# 0-Hierarchy.net
KiCad netlist of a schematic drawn in Altium Designer
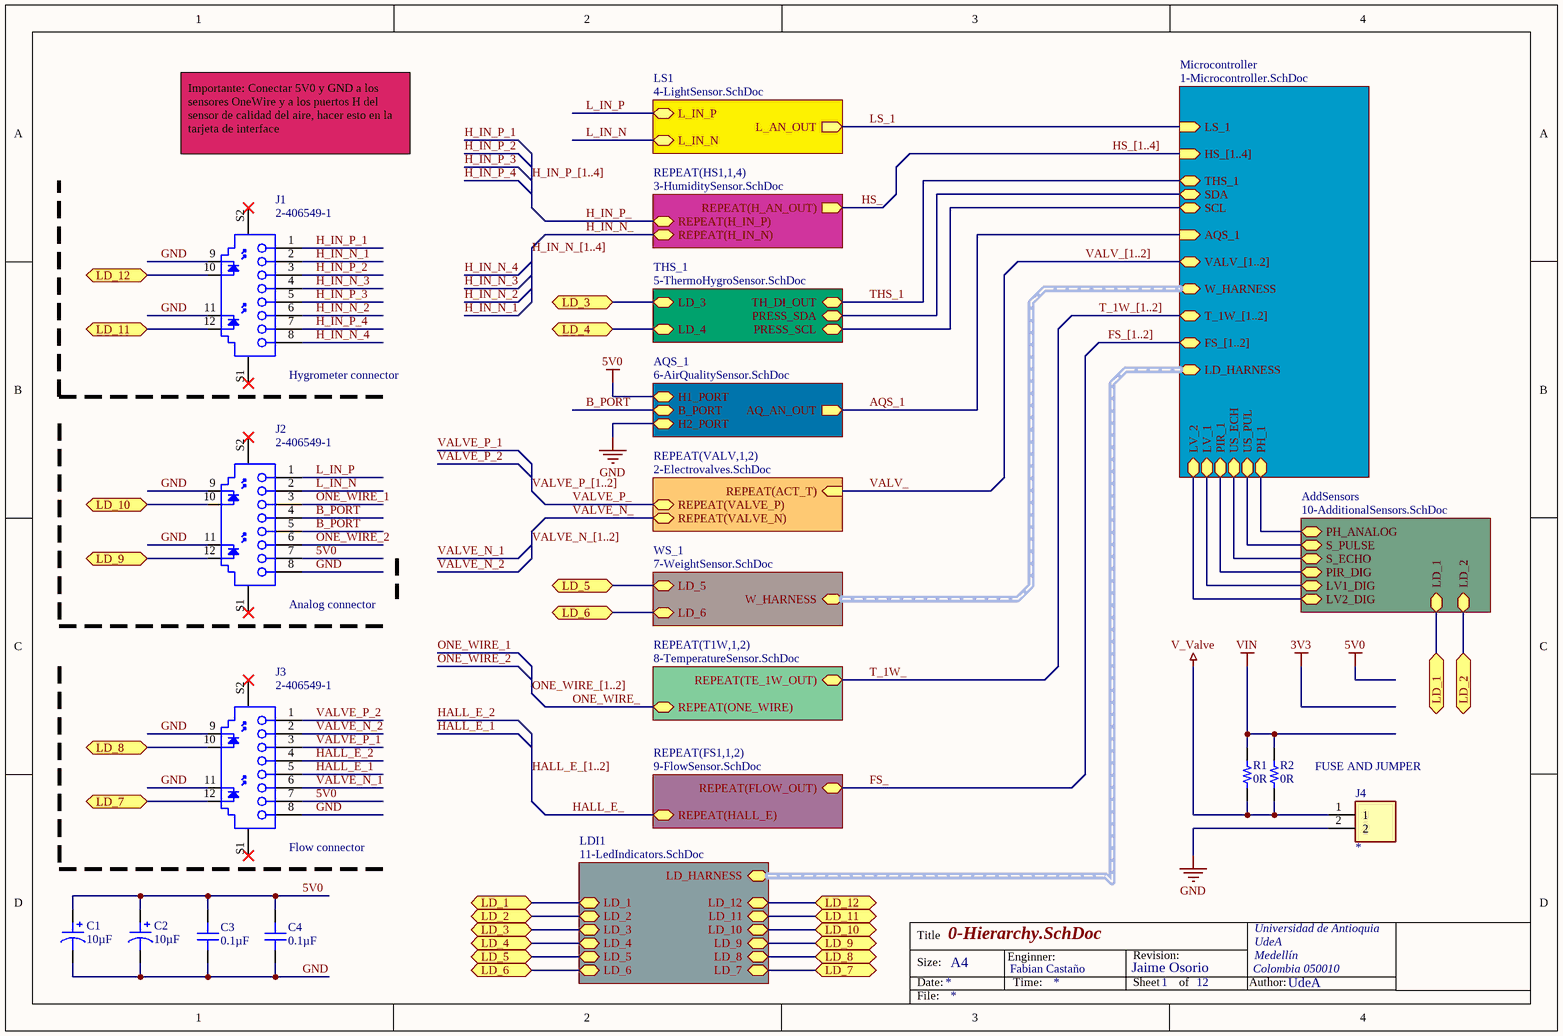
[diagram p0: 0-Hierarchy.SchDoc]

(export (version "E")
  (design (tool "Eeschema 10.0.6"))
  (components
    (comp (ref "C1")
      (value "10µF")
      (footprint "CAP POL 1206_3216")
      (description "CAP TANT POLY 10UF 25V 1206")
      (fields (field (name "PART NUMBER") "TCNK106M025R0350") (field (name "MANUFACTURER") "AVX Corporation"))
      (libsource (lib "Celestial Altium Library - altium_library") (part "Polarised Capacitor"))
    )
    (comp (ref "C2")
      (value "10µF")
      (footprint "CAP POL 1206_3216")
      (description "CAP TANT POLY 10UF 25V 1206")
      (fields (field (name "PART NUMBER") "TCNK106M025R0350") (field (name "MANUFACTURER") "AVX Corporation"))
      (libsource (lib "Celestial Altium Library - altium_library") (part "Polarised Capacitor"))
    )
    (comp (ref "C3")
      (value "0.1µF")
      (footprint "CAP 0805_2012")
      (description "CAP CER 0.1UF 50V X7R 0805")
      (fields (field (name "PART NUMBER") "C0805C104M5RACAUTO") (field (name "MANUFACTURER") "KEMET"))
      (libsource (lib "Celestial Altium Library - altium_library") (part "Capacitor"))
    )
    (comp (ref "C4")
      (value "0.1µF")
      (footprint "CAP 0805_2012")
      (description "CAP CER 0.1UF 50V X7R 0805")
      (fields (field (name "PART NUMBER") "C0805C104M5RACAUTO") (field (name "MANUFACTURER") "KEMET"))
      (libsource (lib "Celestial Altium Library - altium_library") (part "Capacitor"))
    )
    (comp (ref "J1")
      (value "2-406549-1")
      (footprint "TECO-2-406549-1_V")
      (description "RJ45 Connector, Pitch 1.016 mm, 8 Position, Height 14.22 mm, Tail Length 3.18 mm, RoHS, Tray")
      (fields (field (name "MANUFACTURER") "TE Connectivity"))
      (libsource (lib "Altium Content Vault") (part "RJ45-12-2SHLD_A"))
    )
    (comp (ref "J2")
      (value "2-406549-1")
      (footprint "TECO-2-406549-1_V")
      (description "RJ45 Connector, Pitch 1.016 mm, 8 Position, Height 14.22 mm, Tail Length 3.18 mm, RoHS, Tray")
      (fields (field (name "MANUFACTURER") "TE Connectivity"))
      (libsource (lib "Altium Content Vault") (part "RJ45-12-2SHLD_A"))
    )
    (comp (ref "J3")
      (value "2-406549-1")
      (footprint "TECO-2-406549-1_V")
      (description "RJ45 Connector, Pitch 1.016 mm, 8 Position, Height 14.22 mm, Tail Length 3.18 mm, RoHS, Tray")
      (fields (field (name "MANUFACTURER") "TE Connectivity"))
      (libsource (lib "Altium Content Vault") (part "RJ45-12-2SHLD_A"))
    )
    (comp (ref "J4")
      (value "282841-2")
      (footprint "TE_282841-2")
      (description "Conn Terminal Block 2 POS 5.08mm Solder ST Thru-Hole 17.5A/Contact")
      (fields (field (name "MF") "TE Connectivity") (field (name "COMMENT_1") "*"))
      (libsource (lib "PTR500-2") (part "282841-2"))
    )
    (comp (ref "R1")
      (value "0R")
      (footprint "RES 0805_2012")
      (description "RES SMD 1.47K OHM 1% 1/8W 0805")
      (fields (field (name "PART NUMBER") "RC0805FR-071K47L") (field (name "MANUFACTURER") "Yageo"))
      (libsource (lib "Celestial Altium Library - altium_library") (part "Resistor"))
    )
    (comp (ref "R2")
      (value "0R")
      (footprint "RES 0805_2012")
      (description "RES SMD 1.47K OHM 1% 1/8W 0805")
      (fields (field (name "PART NUMBER") "RC0805FR-071K47L") (field (name "MANUFACTURER") "Yageo"))
      (libsource (lib "Celestial Altium Library - altium_library") (part "Resistor"))
    )
  )
  (nets
    (net (code "12") (name "/B_PORT") (class "Default")
      (node (ref "J2") (pin "4") (pinfunction "4_4") (pintype "passive"))
      (node (ref "J2") (pin "5") (pinfunction "5_5") (pintype "passive"))
    )
    (net (code "16") (name "/HALL_E_1") (class "Default")
      (node (ref "J3") (pin "5") (pinfunction "5_5") (pintype "passive"))
    )
    (net (code "17") (name "/HALL_E_2") (class "Default")
      (node (ref "J3") (pin "4") (pinfunction "4_4") (pintype "passive"))
    )
    (net (code "22") (name "/H_IN_N_1") (class "Default")
      (node (ref "J1") (pin "2") (pinfunction "2_2") (pintype "passive"))
    )
    (net (code "23") (name "/H_IN_N_2") (class "Default")
      (node (ref "J1") (pin "6") (pinfunction "6_6") (pintype "passive"))
    )
    (net (code "24") (name "/H_IN_N_3") (class "Default")
      (node (ref "J1") (pin "4") (pinfunction "4_4") (pintype "passive"))
    )
    (net (code "25") (name "/H_IN_N_4") (class "Default")
      (node (ref "J1") (pin "8") (pinfunction "8_8") (pintype "passive"))
    )
    (net (code "28") (name "/H_IN_P_1") (class "Default")
      (node (ref "J1") (pin "1") (pinfunction "1_1") (pintype "passive"))
    )
    (net (code "29") (name "/H_IN_P_2") (class "Default")
      (node (ref "J1") (pin "3") (pinfunction "3_3") (pintype "passive"))
    )
    (net (code "30") (name "/H_IN_P_3") (class "Default")
      (node (ref "J1") (pin "5") (pinfunction "5_5") (pintype "passive"))
    )
    (net (code "31") (name "/H_IN_P_4") (class "Default")
      (node (ref "J1") (pin "7") (pinfunction "7_7") (pintype "passive"))
    )
    (net (code "39") (name "/LD_7") (class "Default")
      (node (ref "J3") (pin "12") (pinfunction "12_12") (pintype "passive"))
    )
    (net (code "40") (name "/LD_8") (class "Default")
      (node (ref "J3") (pin "10") (pinfunction "10_10") (pintype "passive"))
    )
    (net (code "41") (name "/LD_9") (class "Default")
      (node (ref "J2") (pin "12") (pinfunction "12_12") (pintype "passive"))
    )
    (net (code "42") (name "/LD_10") (class "Default")
      (node (ref "J2") (pin "10") (pinfunction "10_10") (pintype "passive"))
    )
    (net (code "43") (name "/LD_11") (class "Default")
      (node (ref "J1") (pin "12") (pinfunction "12_12") (pintype "passive"))
    )
    (net (code "44") (name "/LD_12") (class "Default")
      (node (ref "J1") (pin "10") (pinfunction "10_10") (pintype "passive"))
    )
    (net (code "49") (name "/L_IN_N") (class "Default")
      (node (ref "J2") (pin "2") (pinfunction "2_2") (pintype "passive"))
    )
    (net (code "50") (name "/L_IN_P") (class "Default")
      (node (ref "J2") (pin "1") (pinfunction "1_1") (pintype "passive"))
    )
    (net (code "52") (name "/ONE_WIRE_1") (class "Default")
      (node (ref "J2") (pin "3") (pinfunction "3_3") (pintype "passive"))
    )
    (net (code "53") (name "/ONE_WIRE_2") (class "Default")
      (node (ref "J2") (pin "6") (pinfunction "6_6") (pintype "passive"))
    )
    (net (code "65") (name "/VALVE_N_1") (class "Default")
      (node (ref "J3") (pin "6") (pinfunction "6_6") (pintype "passive"))
    )
    (net (code "66") (name "/VALVE_N_2") (class "Default")
      (node (ref "J3") (pin "2") (pinfunction "2_2") (pintype "passive"))
    )
    (net (code "69") (name "/VALVE_P_1") (class "Default")
      (node (ref "J3") (pin "3") (pinfunction "3_3") (pintype "passive"))
    )
    (net (code "70") (name "/VALVE_P_2") (class "Default")
      (node (ref "J3") (pin "1") (pinfunction "1_1") (pintype "passive"))
    )
    (net (code "76") (name "5V0") (class "Default")
      (node (ref "C1") (pin "1") (pinfunction "1_1") (pintype "passive"))
      (node (ref "C2") (pin "1") (pinfunction "1_1") (pintype "passive"))
      (node (ref "C3") (pin "2") (pinfunction "2_2") (pintype "passive"))
      (node (ref "C4") (pin "2") (pinfunction "2_2") (pintype "passive"))
      (node (ref "J2") (pin "7") (pinfunction "7_7") (pintype "passive"))
      (node (ref "J3") (pin "7") (pinfunction "7_7") (pintype "passive"))
    )
    (net (code "77") (name "GND") (class "Default")
      (node (ref "C1") (pin "2") (pinfunction "2_2") (pintype "passive"))
      (node (ref "C2") (pin "2") (pinfunction "2_2") (pintype "passive"))
      (node (ref "C3") (pin "1") (pinfunction "1_1") (pintype "passive"))
      (node (ref "C4") (pin "1") (pinfunction "1_1") (pintype "passive"))
      (node (ref "J1") (pin "11") (pinfunction "11_11") (pintype "passive"))
      (node (ref "J1") (pin "9") (pinfunction "9_9") (pintype "passive"))
      (node (ref "J2") (pin "11") (pinfunction "11_11") (pintype "passive"))
      (node (ref "J2") (pin "8") (pinfunction "8_8") (pintype "passive"))
      (node (ref "J2") (pin "9") (pinfunction "9_9") (pintype "passive"))
      (node (ref "J3") (pin "11") (pinfunction "11_11") (pintype "passive"))
      (node (ref "J3") (pin "8") (pinfunction "8_8") (pintype "passive"))
      (node (ref "J3") (pin "9") (pinfunction "9_9") (pintype "passive"))
      (node (ref "J4") (pin "2") (pinfunction "2_2") (pintype "passive"))
    )
    (net (code "78") (name "VIN") (class "Default")
      (node (ref "R1") (pin "2") (pinfunction "2_2") (pintype "passive"))
      (node (ref "R2") (pin "2") (pinfunction "2_2") (pintype "passive"))
    )
    (net (code "79") (name "V_Valve") (class "Default")
      (node (ref "J4") (pin "1") (pinfunction "1_1") (pintype "passive"))
      (node (ref "R1") (pin "1") (pinfunction "1_1") (pintype "passive"))
      (node (ref "R2") (pin "1") (pinfunction "1_1") (pintype "passive"))
    )
    (net (code "80") (name "unconnected-(J1-PadS1)") (class "Default")
      (node (ref "J1") (pin "S1") (pinfunction "S1_S1") (pintype "passive+no_connect"))
    )
    (net (code "81") (name "unconnected-(J1-PadS2)") (class "Default")
      (node (ref "J1") (pin "S2") (pinfunction "S2_S2") (pintype "passive+no_connect"))
    )
    (net (code "82") (name "unconnected-(J2-PadS1)") (class "Default")
      (node (ref "J2") (pin "S1") (pinfunction "S1_S1") (pintype "passive+no_connect"))
    )
    (net (code "83") (name "unconnected-(J2-PadS2)") (class "Default")
      (node (ref "J2") (pin "S2") (pinfunction "S2_S2") (pintype "passive+no_connect"))
    )
    (net (code "84") (name "unconnected-(J3-PadS1)") (class "Default")
      (node (ref "J3") (pin "S1") (pinfunction "S1_S1") (pintype "passive+no_connect"))
    )
    (net (code "85") (name "unconnected-(J3-PadS2)") (class "Default")
      (node (ref "J3") (pin "S2") (pinfunction "S2_S2") (pintype "passive+no_connect"))
    )
  )
)
